# test_connector.net
KiCad netlist of a schematic drawn in Altium Designer
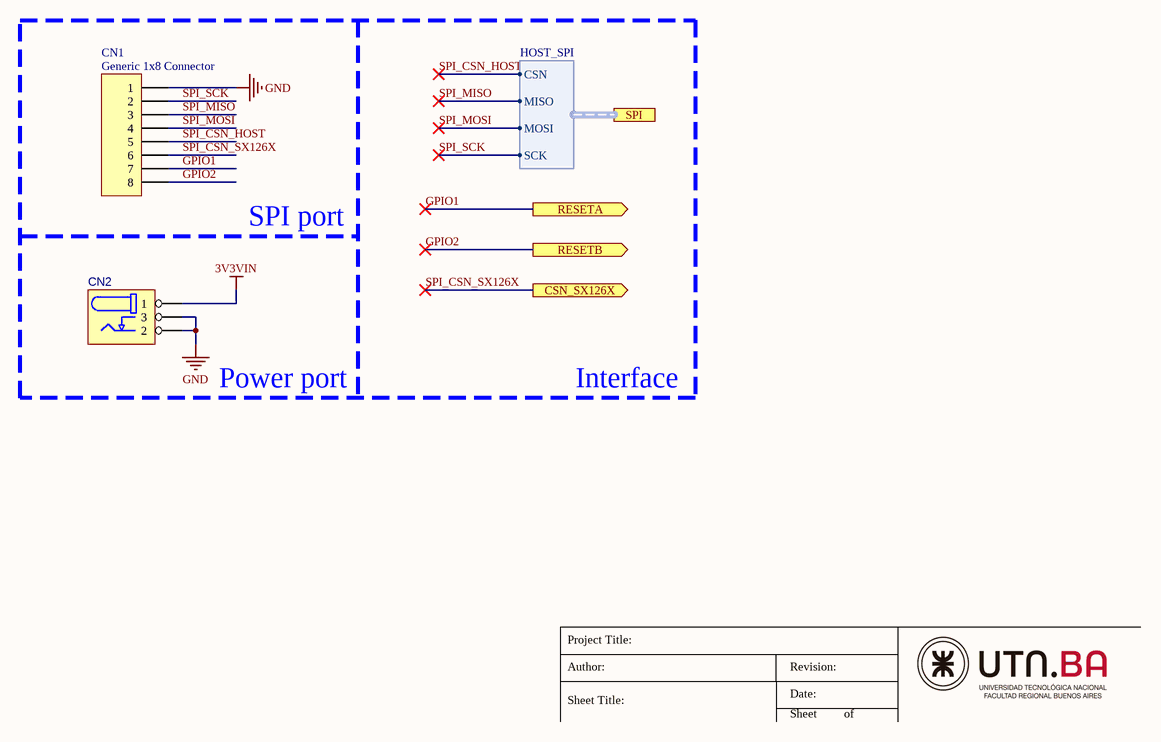
[diagram p0: test_connector.SchDoc]

(export (version "E")
  (design (tool "Eeschema 10.0.6"))
  (components
    (comp (ref "CN1")
      (value "Generic 1x8 Connector")
      (footprint "Header_M_1x8_0.1\"")
      (description "Connector Generic 8 Vias")
      (fields (field (name "MANUFACTURER") "Oupiin") (field (name "MPN") "2011-1X08G00SB"))
      (libsource (lib "lorawan_gateway") (part "CONN_8P"))
    )
    (comp (ref "CN2")
      (value "Barrel Power Connector")
      (footprint "PJ002B")
      (description "CONN PWR JACK 2.5X5.5MM SOLDER")
      (fields (field (name "MANUFACTURER") "CUI Devices") (field (name "MPN") "PJ-002B"))
      (libsource (lib "lorawan_gateway") (part "CN_PowerJack"))
    )
  )
  (nets
    (net (code "2") (name "/GPIO1") (class "Default")
      (node (ref "CN1") (pin "7") (pinfunction "7_7") (pintype "passive+no_connect"))
    )
    (net (code "3") (name "/GPIO2") (class "Default")
      (node (ref "CN1") (pin "8") (pinfunction "8_8") (pintype "passive+no_connect"))
    )
    (net (code "4") (name "/SPI_CSN_HOST") (class "Default")
      (node (ref "CN1") (pin "5") (pinfunction "5_5") (pintype "passive+no_connect"))
    )
    (net (code "5") (name "/SPI_CSN_SX126X") (class "Default")
      (node (ref "CN1") (pin "6") (pinfunction "6_6") (pintype "passive+no_connect"))
    )
    (net (code "6") (name "/SPI_MISO") (class "Default")
      (node (ref "CN1") (pin "3") (pinfunction "3_3") (pintype "passive+no_connect"))
    )
    (net (code "7") (name "/SPI_MOSI") (class "Default")
      (node (ref "CN1") (pin "4") (pinfunction "4_4") (pintype "passive+no_connect"))
    )
    (net (code "8") (name "/SPI_SCK") (class "Default")
      (node (ref "CN1") (pin "2") (pinfunction "2_2") (pintype "passive+no_connect"))
    )
    (net (code "10") (name "3V3VIN") (class "Default")
      (node (ref "CN2") (pin "1") (pinfunction "1_1") (pintype "passive"))
    )
    (net (code "11") (name "GND") (class "Default")
      (node (ref "CN1") (pin "1") (pinfunction "1_1") (pintype "passive"))
      (node (ref "CN2") (pin "2") (pinfunction "2_2") (pintype "passive"))
      (node (ref "CN2") (pin "3") (pinfunction "3_3") (pintype "passive"))
    )
  )
)
